# SVPXGR740_3U.net
KiCad netlist of a schematic drawn in Altium Designer
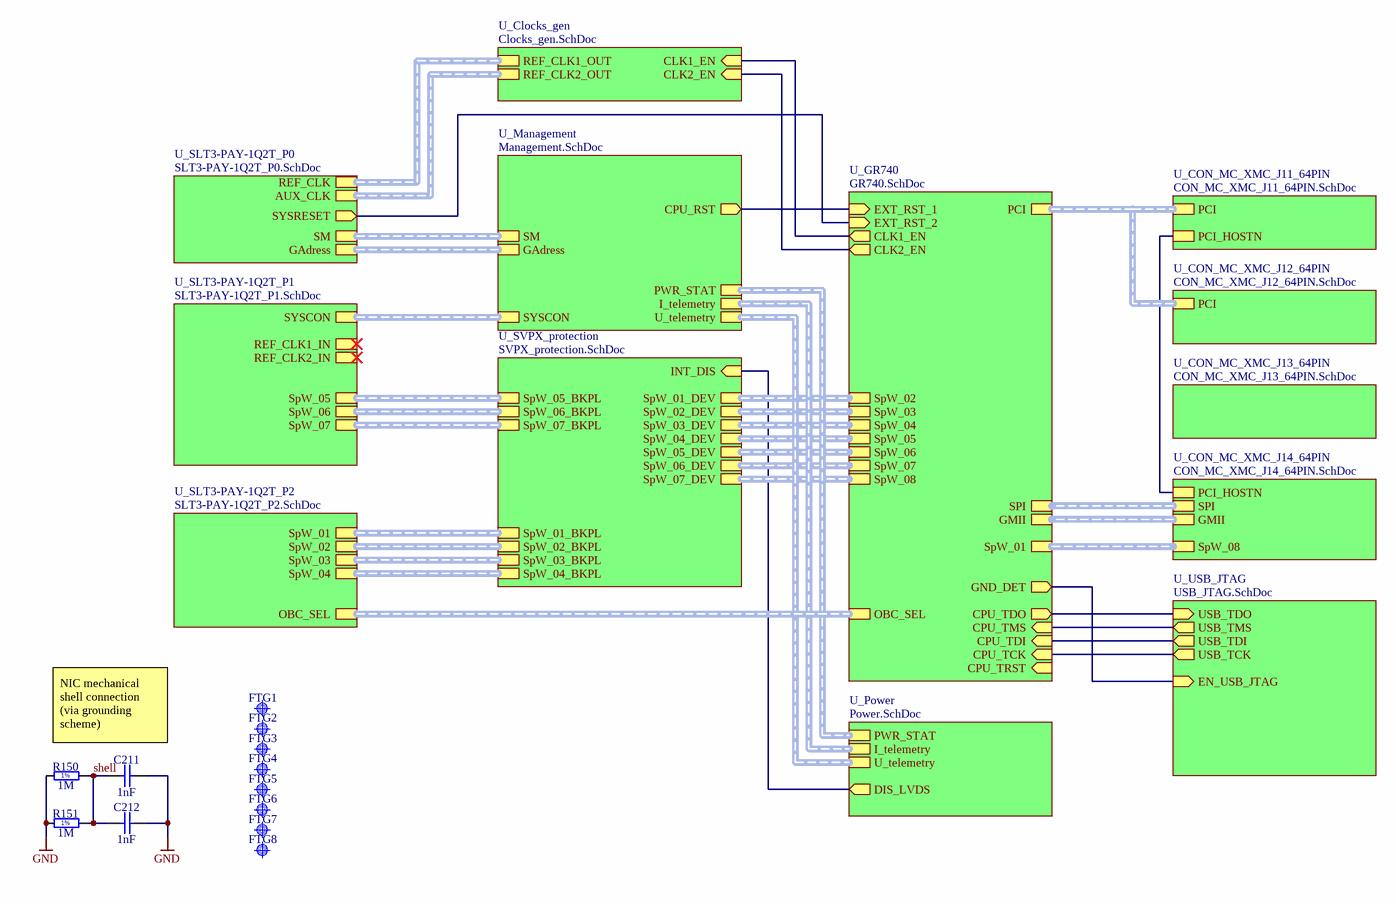
[diagram p0: SVPXGR740_3U.SchDoc]

(export (version "E")
  (design (tool "Eeschema 10.0.6"))
  (components
    (comp (ref "C211")
      (value "1nF")
      (footprint "CAPC1005X55N")
      (description "Non-polarised capacitor")
      (fields
        (field (name "PART NUMBER") "CC0402_1NF_50V_10%_X7R")
        (field (name "VOLTAGE") "50V")
        (field (name "AUTHOR") "CERN DEM JLC")
      )
      (libsource (lib "Capacitors") (part "Capacitor - non polarized"))
    )
    (comp (ref "C212")
      (value "1nF")
      (footprint "CAPC1005X55N")
      (description "Non-polarised capacitor")
      (fields
        (field (name "PART NUMBER") "CC0402_1NF_50V_10%_X7R")
        (field (name "VOLTAGE") "50V")
        (field (name "AUTHOR") "CERN DEM JLC")
      )
      (libsource (lib "Capacitors") (part "Capacitor - non polarized"))
    )
    (comp (ref "FTG1")
      (value "Use only in PCB")
      (footprint "FIDUCIAL_TOP_C100-200")
      (description "Fiducial Target")
      (fields (field (name "PART NUMBER") "FIDUCIAL_TARGET_C100-200") (field (name "AUTHOR") "CERN DEM JLC"))
      (libsource (lib "Eletro-mechanical") (part "Fiducial Target"))
    )
    (comp (ref "FTG2")
      (value "Use only in PCB")
      (footprint "FIDUCIAL_TOP_C100-200")
      (description "Fiducial Target")
      (fields (field (name "PART NUMBER") "FIDUCIAL_TARGET_C100-200") (field (name "AUTHOR") "CERN DEM JLC"))
      (libsource (lib "Eletro-mechanical") (part "Fiducial Target"))
    )
    (comp (ref "FTG3")
      (value "Use only in PCB")
      (footprint "FIDUCIAL_TOP_C100-200")
      (description "Fiducial Target")
      (fields (field (name "PART NUMBER") "FIDUCIAL_TARGET_C100-200") (field (name "AUTHOR") "CERN DEM JLC"))
      (libsource (lib "Eletro-mechanical") (part "Fiducial Target"))
    )
    (comp (ref "FTG4")
      (value "Use only in PCB")
      (footprint "FIDUCIAL_TOP_C100-200")
      (description "Fiducial Target")
      (fields (field (name "PART NUMBER") "FIDUCIAL_TARGET_C100-200") (field (name "AUTHOR") "CERN DEM JLC"))
      (libsource (lib "Eletro-mechanical") (part "Fiducial Target"))
    )
    (comp (ref "FTG5")
      (value "Use only in PCB")
      (footprint "FIDUCIAL_TOP_C100-200")
      (description "Fiducial Target")
      (fields (field (name "PART NUMBER") "FIDUCIAL_TARGET_C100-200") (field (name "AUTHOR") "CERN DEM JLC"))
      (libsource (lib "Eletro-mechanical") (part "Fiducial Target"))
    )
    (comp (ref "FTG6")
      (value "Use only in PCB")
      (footprint "FIDUCIAL_TOP_C100-200")
      (description "Fiducial Target")
      (fields (field (name "PART NUMBER") "FIDUCIAL_TARGET_C100-200") (field (name "AUTHOR") "CERN DEM JLC"))
      (libsource (lib "Eletro-mechanical") (part "Fiducial Target"))
    )
    (comp (ref "FTG7")
      (value "Use only in PCB")
      (footprint "FIDUCIAL_TOP_C100-200")
      (description "Fiducial Target")
      (fields (field (name "PART NUMBER") "FIDUCIAL_TARGET_C100-200") (field (name "AUTHOR") "CERN DEM JLC"))
      (libsource (lib "Eletro-mechanical") (part "Fiducial Target"))
    )
    (comp (ref "FTG8")
      (value "Use only in PCB")
      (footprint "FIDUCIAL_TOP_C100-200")
      (description "Fiducial Target")
      (fields (field (name "PART NUMBER") "FIDUCIAL_TARGET_C100-200") (field (name "AUTHOR") "CERN DEM JLC"))
      (libsource (lib "Eletro-mechanical") (part "Fiducial Target"))
    )
    (comp (ref "R150")
      (value "1M")
      (footprint "RESC1005X40N")
      (description "Resistor - 1%")
      (fields
        (field (name "PART NUMBER") "R0402_1M_1%_0.0625W_100PPM")
        (field (name "POWER") "0.0625W")
        (field (name "AUTHOR") "CERN DEM JLC")
      )
      (libsource (lib "Resistors") (part "Resistor - 1%"))
    )
    (comp (ref "R151")
      (value "1M")
      (footprint "RESC1005X40N")
      (description "Resistor - 1%")
      (fields
        (field (name "PART NUMBER") "R0402_1M_1%_0.0625W_100PPM")
        (field (name "POWER") "0.0625W")
        (field (name "AUTHOR") "CERN DEM JLC")
      )
      (libsource (lib "Resistors") (part "Resistor - 1%"))
    )
  )
  (nets
    (net (code "42") (name "/shell") (class "Default")
      (node (ref "C211") (pin "1") (pinfunction "1_1") (pintype "passive"))
      (node (ref "C212") (pin "1") (pinfunction "1_1") (pintype "passive"))
      (node (ref "R150") (pin "2") (pinfunction "2_2") (pintype "passive"))
      (node (ref "R151") (pin "2") (pinfunction "2_2") (pintype "passive"))
    )
    (net (code "43") (name "GND") (class "Default")
      (node (ref "C211") (pin "2") (pinfunction "2_2") (pintype "passive"))
      (node (ref "C212") (pin "2") (pinfunction "2_2") (pintype "passive"))
      (node (ref "R150") (pin "1") (pinfunction "1_1") (pintype "passive"))
      (node (ref "R151") (pin "1") (pinfunction "1_1") (pintype "passive"))
    )
  )
)
